# EMG_FSR.net
KiCad netlist of a schematic drawn in EAGLE
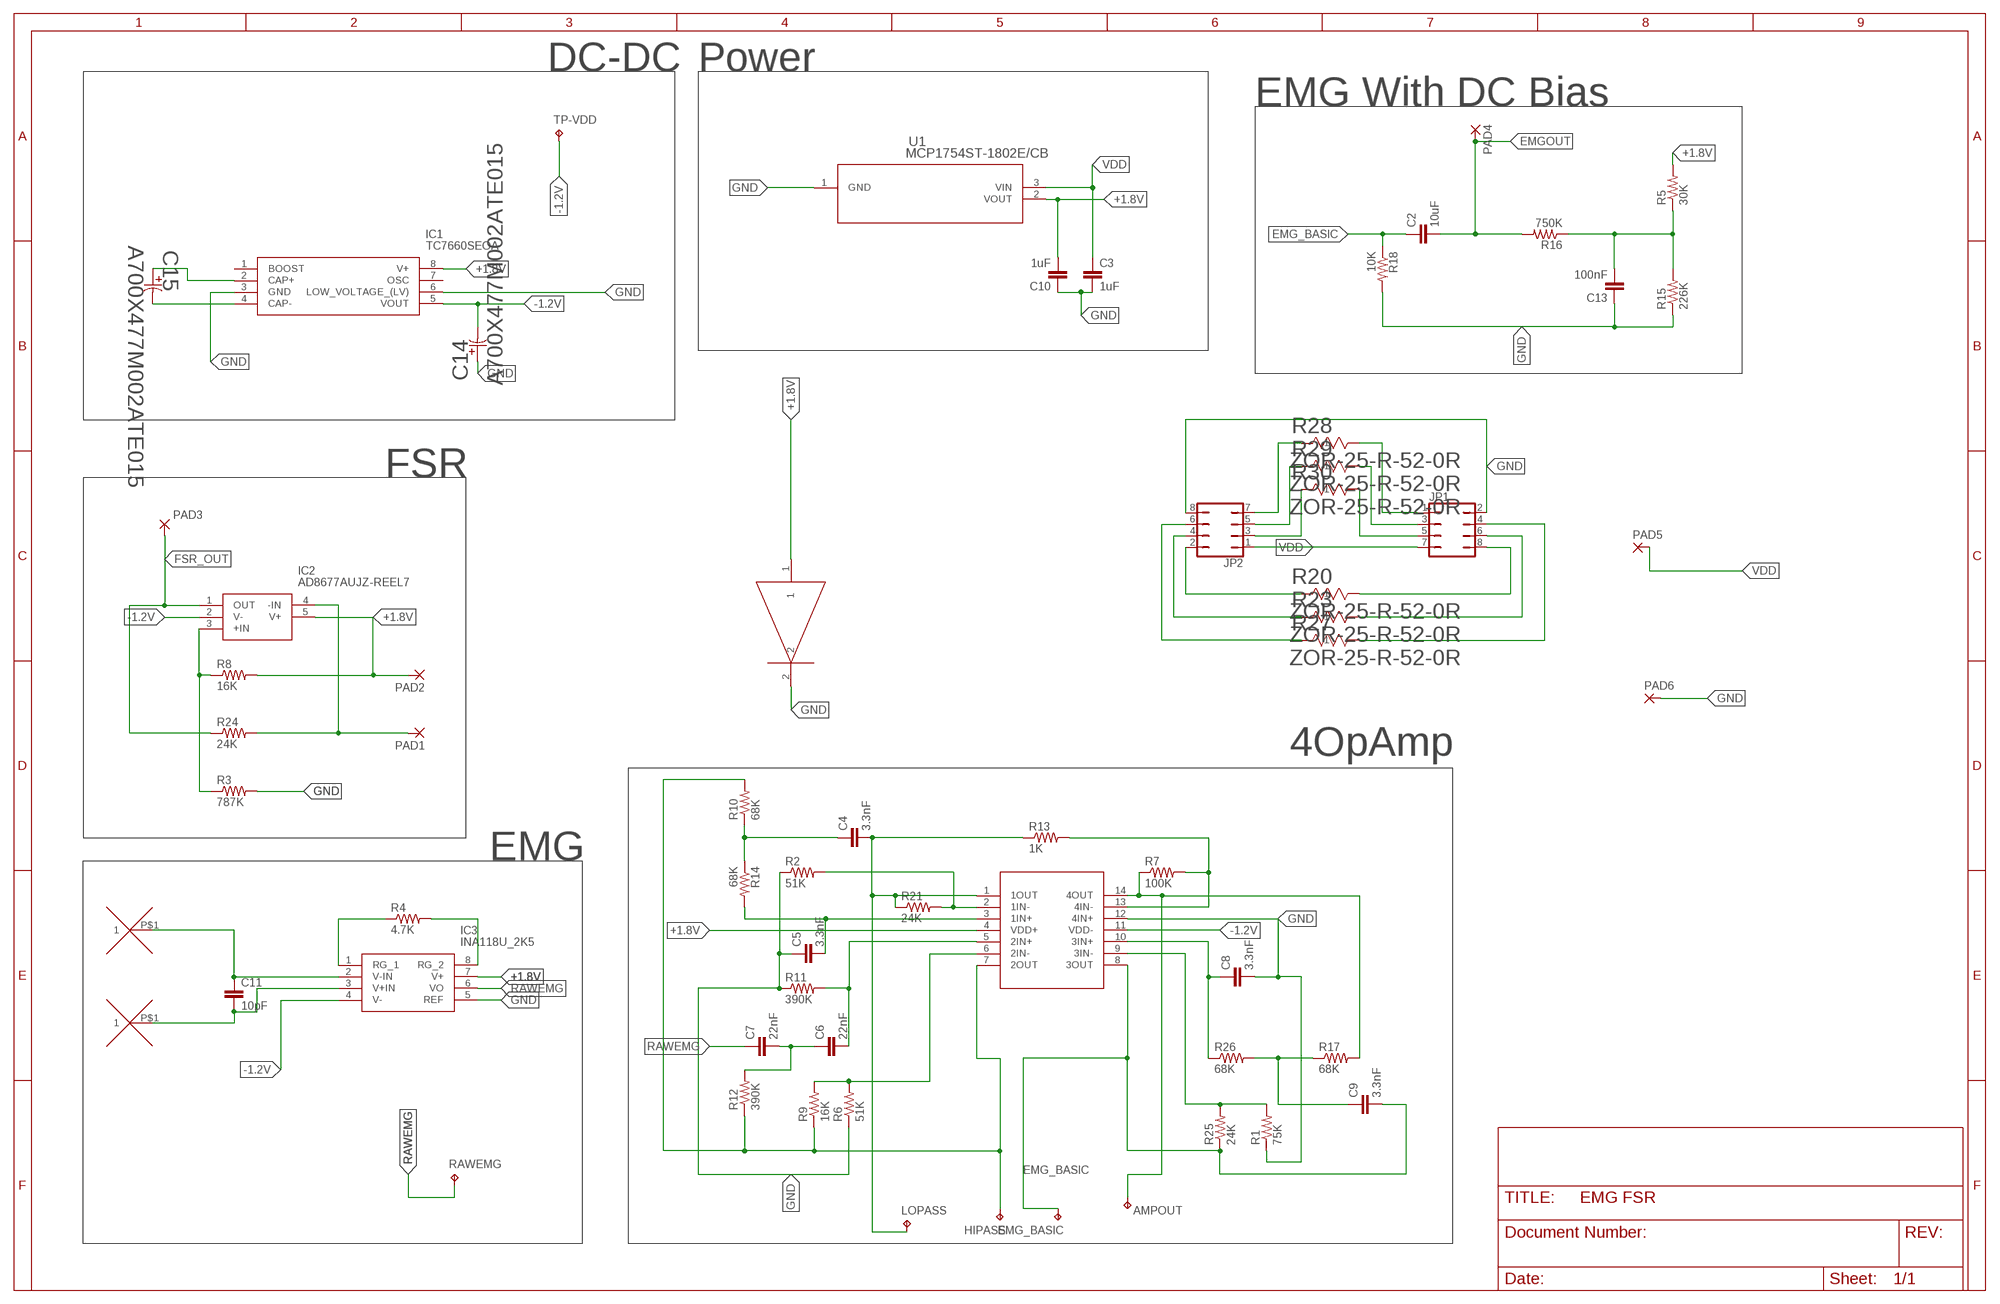
[diagram p0: schematic, sheet 1]

(export (version "E")
  (design (tool "Eeschema 10.0.6"))
  (components
    (comp (ref "AMPOUT")
      (value "TPTP08R")
      (footprint "eagle-import:TP08R")
      (libsource (lib "eagle-import") (part "TPTP08R"))
    )
    (comp (ref "C2")
      (value "10uF")
      (footprint "eagle-import:C0402")
      (libsource (lib "eagle-import") (part "rcl_334_C-EUC0402"))
    )
    (comp (ref "C3")
      (value "1uF")
      (footprint "eagle-import:C0402")
      (libsource (lib "eagle-import") (part "rcl_334_C-EUC0402"))
    )
    (comp (ref "C4")
      (value "3.3nF")
      (footprint "eagle-import:C1206")
      (libsource (lib "eagle-import") (part "C-EUC1206"))
    )
    (comp (ref "C5")
      (value "3.3nF")
      (footprint "eagle-import:C1206")
      (libsource (lib "eagle-import") (part "C-EUC1206"))
    )
    (comp (ref "C6")
      (value "22nF")
      (footprint "eagle-import:C0805")
      (libsource (lib "eagle-import") (part "C-EUC0805"))
    )
    (comp (ref "C7")
      (value "22nF")
      (footprint "eagle-import:C0805")
      (libsource (lib "eagle-import") (part "C-EUC0805"))
    )
    (comp (ref "C8")
      (value "3.3nF")
      (footprint "eagle-import:C1206")
      (libsource (lib "eagle-import") (part "C-EUC1206"))
    )
    (comp (ref "C9")
      (value "3.3nF")
      (footprint "eagle-import:C1206")
      (libsource (lib "eagle-import") (part "C-EUC1206"))
    )
    (comp (ref "C10")
      (value "1uF")
      (footprint "eagle-import:C0402")
      (libsource (lib "eagle-import") (part "rcl_334_C-EUC0402"))
    )
    (comp (ref "C11")
      (value "10pF")
      (footprint "eagle-import:C0402")
      (libsource (lib "eagle-import") (part "rcl_334_C-EUC0402"))
    )
    (comp (ref "C13")
      (value "100nF")
      (footprint "eagle-import:C0402")
      (libsource (lib "eagle-import") (part "rcl_334_C-EUC0402"))
    )
    (comp (ref "C14")
      (value "A700X477M002ATE015")
      (footprint "eagle-import:PCAP7343-43_KEMET_KEM")
      (libsource (lib "eagle-import") (part "A700X477M002ATE015"))
    )
    (comp (ref "C15")
      (value "A700X477M002ATE015")
      (footprint "eagle-import:PCAP7343-43_KEMET_KEM")
      (libsource (lib "eagle-import") (part "A700X477M002ATE015"))
    )
    (comp (ref "EMG_BASIC")
      (value "TPTP08R")
      (footprint "eagle-import:TP08R")
      (libsource (lib "eagle-import") (part "TPTP08R"))
    )
    (comp (ref "HIPASS")
      (value "TPTP08R")
      (footprint "eagle-import:TP08R")
      (libsource (lib "eagle-import") (part "TPTP08R"))
    )
    (comp (ref "IC1")
      (value "TC7660SEOA")
      (footprint "eagle-import:SOIC127P600X175-8N")
      (fields (field (name "MOUSER_PART_NUMBER") "579-TC7660SEOA"))
      (libsource (lib "eagle-import") (part "TC7660SEOA"))
    )
    (comp (ref "IC2")
      (value "AD8677AUJZ-REEL7")
      (footprint "eagle-import:SOT95P280X100-5N")
      (fields (field (name "MOUSER_PART_NUMBER") "584-AD8677AUJZ-R7"))
      (libsource (lib "eagle-import") (part "AD8677AUJZ-REEL7"))
    )
    (comp (ref "IC3")
      (value "INA118U_2K5")
      (footprint "eagle-import:SOIC127P600X175-8N")
      (fields
        (field (name "ARROW_PART_NUMBER") "INA118U/2K5")
        (field (name "MOUSER_PART_NUMBER") "595-INA118U/2K5")
      )
      (libsource (lib "eagle-import") (part "INA118U_2K5"))
    )
    (comp (ref "JP1")
      (value "JP4Q")
      (footprint "eagle-import:JP4Q")
      (libsource (lib "eagle-import") (part "JP4Q"))
    )
    (comp (ref "JP2")
      (value "JP4Q")
      (footprint "eagle-import:JP4Q")
      (libsource (lib "eagle-import") (part "JP4Q"))
    )
    (comp (ref "LOPASS")
      (value "TPTP08R")
      (footprint "eagle-import:TP08R")
      (libsource (lib "eagle-import") (part "TPTP08R"))
    )
    (comp (ref "PAD1")
      (value "SMD2")
      (footprint "eagle-import:SMD1,27-2,54")
      (libsource (lib "eagle-import") (part "SMD2"))
    )
    (comp (ref "PAD2")
      (value "SMD2")
      (footprint "eagle-import:SMD1,27-2,54")
      (libsource (lib "eagle-import") (part "SMD2"))
    )
    (comp (ref "PAD3")
      (value "1,6/0,8")
      (footprint "eagle-import:1,6_0,8")
      (libsource (lib "eagle-import") (part "1,6/0,8"))
    )
    (comp (ref "PAD4")
      (value "1,6/0,8")
      (footprint "eagle-import:1,6_0,8")
      (libsource (lib "eagle-import") (part "1,6/0,8"))
    )
    (comp (ref "PAD5")
      (value "1,6/0,8")
      (footprint "eagle-import:1,6_0,8")
      (libsource (lib "eagle-import") (part "1,6/0,8"))
    )
    (comp (ref "PAD6")
      (value "1,6/0,8")
      (footprint "eagle-import:1,6_0,8")
      (libsource (lib "eagle-import") (part "1,6/0,8"))
    )
    (comp (ref "R1")
      (value "75K")
      (footprint "eagle-import:R0402")
      (libsource (lib "eagle-import") (part "adafruit_420_R-US_R0402"))
    )
    (comp (ref "R2")
      (value "51K")
      (footprint "eagle-import:R0402")
      (libsource (lib "eagle-import") (part "adafruit_420_R-US_R0402"))
    )
    (comp (ref "R3")
      (value "787K")
      (footprint "eagle-import:R0805")
      (libsource (lib "eagle-import") (part "rcl_R-US_R0805"))
    )
    (comp (ref "R4")
      (value "4.7K")
      (footprint "eagle-import:R0402")
      (libsource (lib "eagle-import") (part "adafruit@1_R-US_R0402"))
    )
    (comp (ref "R5")
      (value "30K")
      (footprint "eagle-import:R0402")
      (libsource (lib "eagle-import") (part "adafruit_420_R-US_R0402"))
    )
    (comp (ref "R6")
      (value "51K")
      (footprint "eagle-import:R0402")
      (libsource (lib "eagle-import") (part "adafruit_420_R-US_R0402"))
    )
    (comp (ref "R7")
      (value "100K")
      (footprint "eagle-import:R1005")
      (libsource (lib "eagle-import") (part "adafruit@1_R-US_R1005"))
    )
    (comp (ref "R8")
      (value "16K")
      (footprint "eagle-import:R0402")
      (libsource (lib "eagle-import") (part "adafruit_420_R-US_R0402"))
    )
    (comp (ref "R9")
      (value "16K")
      (footprint "eagle-import:R0402")
      (libsource (lib "eagle-import") (part "adafruit_420_R-US_R0402"))
    )
    (comp (ref "R10")
      (value "68K")
      (footprint "eagle-import:R0402")
      (libsource (lib "eagle-import") (part "adafruit_420_R-US_R0402"))
    )
    (comp (ref "R11")
      (value "390K")
      (footprint "eagle-import:R0603")
      (libsource (lib "eagle-import") (part "R-US_R0603"))
    )
    (comp (ref "R12")
      (value "390K")
      (footprint "eagle-import:R0603")
      (libsource (lib "eagle-import") (part "adafruit@1_R-US_R0603"))
    )
    (comp (ref "R13")
      (value "1K")
      (footprint "eagle-import:R0402")
      (libsource (lib "eagle-import") (part "adafruit_420_R-US_R0402"))
    )
    (comp (ref "R14")
      (value "68K")
      (footprint "eagle-import:R0402")
      (libsource (lib "eagle-import") (part "adafruit_420_R-US_R0402"))
    )
    (comp (ref "R15")
      (value "226K")
      (footprint "eagle-import:R0402")
      (libsource (lib "eagle-import") (part "adafruit_420_R-US_R0402"))
    )
    (comp (ref "R16")
      (value "750K")
      (footprint "eagle-import:R0402")
      (libsource (lib "eagle-import") (part "adafruit_420_R-US_R0402"))
    )
    (comp (ref "R17")
      (value "68K")
      (footprint "eagle-import:R0402")
      (libsource (lib "eagle-import") (part "adafruit_420_R-US_R0402"))
    )
    (comp (ref "R18")
      (value "10K")
      (footprint "eagle-import:R0402")
      (libsource (lib "eagle-import") (part "adafruit_420_R-US_R0402"))
    )
    (comp (ref "R20")
      (value "ZOR-25-R-52-0R")
      (footprint "eagle-import:RES_ZOR25_6P3X2P3_YAG")
      (fields (field (name "COPYRIGHT") "Copyright (C) 2018 Accelerated Designs. All rights reserved"))
      (libsource (lib "eagle-import") (part "ZOR-25-R-52-0R"))
    )
    (comp (ref "R21")
      (value "24K")
      (footprint "eagle-import:R0402")
      (libsource (lib "eagle-import") (part "adafruit_420_R-US_R0402"))
    )
    (comp (ref "R23")
      (value "ZOR-25-R-52-0R")
      (footprint "eagle-import:RES_ZOR25_6P3X2P3_YAG")
      (fields (field (name "COPYRIGHT") "Copyright (C) 2018 Accelerated Designs. All rights reserved"))
      (libsource (lib "eagle-import") (part "ZOR-25-R-52-0R"))
    )
    (comp (ref "R24")
      (value "24K")
      (footprint "eagle-import:R0402")
      (libsource (lib "eagle-import") (part "adafruit_420_R-US_R0402"))
    )
    (comp (ref "R25")
      (value "24K")
      (footprint "eagle-import:R0402")
      (libsource (lib "eagle-import") (part "adafruit_420_R-US_R0402"))
    )
    (comp (ref "R26")
      (value "68K")
      (footprint "eagle-import:R0402")
      (libsource (lib "eagle-import") (part "adafruit_420_R-US_R0402"))
    )
    (comp (ref "R27")
      (value "ZOR-25-R-52-0R")
      (footprint "eagle-import:RES_ZOR25_6P3X2P3_YAG")
      (fields (field (name "COPYRIGHT") "Copyright (C) 2018 Accelerated Designs. All rights reserved"))
      (libsource (lib "eagle-import") (part "ZOR-25-R-52-0R"))
    )
    (comp (ref "R28")
      (value "ZOR-25-R-52-0R")
      (footprint "eagle-import:RES_ZOR25_6P3X2P3_YAG")
      (fields (field (name "COPYRIGHT") "Copyright (C) 2018 Accelerated Designs. All rights reserved"))
      (libsource (lib "eagle-import") (part "ZOR-25-R-52-0R"))
    )
    (comp (ref "R29")
      (value "ZOR-25-R-52-0R")
      (footprint "eagle-import:RES_ZOR25_6P3X2P3_YAG")
      (fields (field (name "COPYRIGHT") "Copyright (C) 2018 Accelerated Designs. All rights reserved"))
      (libsource (lib "eagle-import") (part "ZOR-25-R-52-0R"))
    )
    (comp (ref "R30")
      (value "ZOR-25-R-52-0R")
      (footprint "eagle-import:RES_ZOR25_6P3X2P3_YAG")
      (fields (field (name "COPYRIGHT") "Copyright (C) 2018 Accelerated Designs. All rights reserved"))
      (libsource (lib "eagle-import") (part "ZOR-25-R-52-0R"))
    )
    (comp (ref "RAWEMG")
      (value "TPTP08R")
      (footprint "eagle-import:TP08R")
      (libsource (lib "eagle-import") (part "TPTP08R"))
    )
    (comp (ref "RED")
      (value "RESC0402X40N")
      (footprint "eagle-import:RESC0402X40N")
      (fields (field (name "MANUFACTURER") "KOA"))
      (libsource (lib "eagle-import") (part "RESC0402X40N"))
    )
    (comp (ref "TP-VDD")
      (value "TPTP08R")
      (footprint "eagle-import:TP08R")
      (libsource (lib "eagle-import") (part "TPTP08R"))
    )
    (comp (ref "U$1")
      (value "TLC2274-HT")
      (footprint "eagle-import:SOP65P640X120-14N")
      (libsource (lib "eagle-import") (part "TLC2274-HT"))
    )
    (comp (ref "U$2")
      (value "EMG_VIA")
      (footprint "eagle-import:EMG_VIA")
      (libsource (lib "eagle-import") (part "EMG_VIA"))
    )
    (comp (ref "U$3")
      (value "EMG_VIA")
      (footprint "eagle-import:EMG_VIA")
      (libsource (lib "eagle-import") (part "EMG_VIA"))
    )
    (comp (ref "U1")
      (value "MCP1754ST-1802E/CB")
      (footprint "eagle-import:SOT-23A_MC_MCH")
      (fields (field (name "COPYRIGHT") "Copyright (C) 2018 Accelerated Designs. All rights reserved"))
      (libsource (lib "eagle-import") (part "MCP1754ST-1802E/CB"))
    )
  )
  (nets
    (net (code "1") (name "+1.8V") (class "Default")
      (node (ref "C10") (pin "2") (pinfunction "2_2") (pintype "passive"))
      (node (ref "IC1") (pin "8") (pinfunction "V+_8") (pintype "bidirectional"))
      (node (ref "IC2") (pin "5") (pinfunction "V+_5") (pintype "bidirectional"))
      (node (ref "IC3") (pin "7") (pinfunction "V+_7") (pintype "bidirectional"))
      (node (ref "PAD2") (pin "1") (pinfunction "P_1") (pintype "passive"))
      (node (ref "R5") (pin "2") (pinfunction "2_2") (pintype "passive"))
      (node (ref "R8") (pin "2") (pinfunction "2_2") (pintype "passive"))
      (node (ref "RED") (pin "1") (pinfunction "1_1") (pintype "bidirectional"))
      (node (ref "U$1") (pin "4") (pinfunction "VDD+_4") (pintype "bidirectional"))
      (node (ref "U1") (pin "2") (pinfunction "VOUT_2") (pintype "output"))
    )
    (net (code "2") (name "-1.2V") (class "Default")
      (node (ref "C14") (pin "2") (pinfunction "2_2") (pintype "passive"))
      (node (ref "IC1") (pin "5") (pinfunction "VOUT_5") (pintype "bidirectional"))
      (node (ref "IC2") (pin "2") (pinfunction "V-_2") (pintype "bidirectional"))
      (node (ref "IC3") (pin "4") (pinfunction "V-_4") (pintype "bidirectional"))
      (node (ref "TP-VDD") (pin "TP") (pinfunction "TP_TP") (pintype "input"))
      (node (ref "U$1") (pin "11") (pinfunction "VDD-_11") (pintype "bidirectional"))
    )
    (net (code "3") (name "EMGOUT") (class "Default")
      (node (ref "C2") (pin "2") (pinfunction "2_2") (pintype "passive"))
      (node (ref "PAD4") (pin "1") (pinfunction "P_1") (pintype "passive"))
      (node (ref "R16") (pin "2") (pinfunction "2_2") (pintype "passive"))
    )
    (net (code "4") (name "EMG_BASIC") (class "Default")
      (node (ref "C2") (pin "1") (pinfunction "1_1") (pintype "passive"))
      (node (ref "C9") (pin "2") (pinfunction "2_2") (pintype "passive"))
      (node (ref "EMG_BASIC") (pin "TP") (pinfunction "TP_TP") (pintype "input"))
      (node (ref "R18") (pin "1") (pinfunction "1_1") (pintype "passive"))
      (node (ref "R25") (pin "1") (pinfunction "1_1") (pintype "passive"))
      (node (ref "U$1") (pin "8") (pinfunction "3OUT_8") (pintype "bidirectional"))
    )
    (net (code "5") (name "FSR_OUT") (class "Default")
      (node (ref "IC2") (pin "1") (pinfunction "OUT_1") (pintype "output"))
      (node (ref "PAD3") (pin "1") (pinfunction "P_1") (pintype "passive"))
      (node (ref "R24") (pin "1") (pinfunction "1_1") (pintype "passive"))
    )
    (net (code "6") (name "GND") (class "Default")
      (node (ref "C10") (pin "1") (pinfunction "1_1") (pintype "passive"))
      (node (ref "C13") (pin "1") (pinfunction "1_1") (pintype "passive"))
      (node (ref "C14") (pin "1") (pinfunction "1_1") (pintype "passive"))
      (node (ref "C3") (pin "2") (pinfunction "2_2") (pintype "passive"))
      (node (ref "C5") (pin "1") (pinfunction "1_1") (pintype "passive"))
      (node (ref "C8") (pin "2") (pinfunction "2_2") (pintype "passive"))
      (node (ref "IC1") (pin "3") (pinfunction "GND_3") (pintype "bidirectional"))
      (node (ref "IC1") (pin "6") (pinfunction "LOW_VOLTAGE_(LV)_6") (pintype "bidirectional"))
      (node (ref "IC3") (pin "5") (pinfunction "REF_5") (pintype "bidirectional"))
      (node (ref "JP1") (pin "2") (pinfunction "2_2") (pintype "passive"))
      (node (ref "JP2") (pin "8") (pinfunction "8_8") (pintype "passive"))
      (node (ref "PAD6") (pin "1") (pinfunction "P_1") (pintype "passive"))
      (node (ref "R1") (pin "1") (pinfunction "1_1") (pintype "passive"))
      (node (ref "R11") (pin "1") (pinfunction "1_1") (pintype "passive"))
      (node (ref "R15") (pin "1") (pinfunction "1_1") (pintype "passive"))
      (node (ref "R18") (pin "2") (pinfunction "2_2") (pintype "passive"))
      (node (ref "R2") (pin "1") (pinfunction "1_1") (pintype "passive"))
      (node (ref "R3") (pin "2") (pinfunction "2_2") (pintype "passive"))
      (node (ref "R6") (pin "1") (pinfunction "1_1") (pintype "passive"))
      (node (ref "RED") (pin "2") (pinfunction "2_2") (pintype "bidirectional"))
      (node (ref "U$1") (pin "12") (pinfunction "4IN+_12") (pintype "bidirectional"))
      (node (ref "U1") (pin "1") (pinfunction "GND_1") (pintype "power_in"))
    )
    (net (code "7") (name "Net-(C4-Pad1)") (class "Default")
      (node (ref "C4") (pin "1") (pinfunction "1_1") (pintype "passive"))
      (node (ref "R10") (pin "1") (pinfunction "1_1") (pintype "passive"))
      (node (ref "R14") (pin "1") (pinfunction "1_1") (pintype "passive"))
    )
    (net (code "8") (name "Net-(C6-Pad1)") (class "Default")
      (node (ref "C6") (pin "1") (pinfunction "1_1") (pintype "passive"))
      (node (ref "C7") (pin "2") (pinfunction "2_2") (pintype "passive"))
      (node (ref "R12") (pin "2") (pinfunction "2_2") (pintype "passive"))
    )
    (net (code "9") (name "Net-(C9-Pad1)") (class "Default")
      (node (ref "C9") (pin "1") (pinfunction "1_1") (pintype "passive"))
      (node (ref "R17") (pin "1") (pinfunction "1_1") (pintype "passive"))
      (node (ref "R26") (pin "2") (pinfunction "2_2") (pintype "passive"))
    )
    (net (code "10") (name "Net-(C13-Pad2)") (class "Default")
      (node (ref "C13") (pin "2") (pinfunction "2_2") (pintype "passive"))
      (node (ref "R15") (pin "2") (pinfunction "2_2") (pintype "passive"))
      (node (ref "R16") (pin "1") (pinfunction "1_1") (pintype "passive"))
      (node (ref "R5") (pin "1") (pinfunction "1_1") (pintype "passive"))
    )
    (net (code "11") (name "Net-(IC1-CAP+)") (class "Default")
      (node (ref "C15") (pin "1") (pinfunction "1_1") (pintype "passive"))
      (node (ref "IC1") (pin "2") (pinfunction "CAP+_2") (pintype "bidirectional"))
    )
    (net (code "12") (name "Net-(IC1-CAP-)") (class "Default")
      (node (ref "C15") (pin "2") (pinfunction "2_2") (pintype "passive"))
      (node (ref "IC1") (pin "4") (pinfunction "CAP-_4") (pintype "bidirectional"))
    )
    (net (code "13") (name "Net-(IC2-+IN)") (class "Default")
      (node (ref "IC2") (pin "3") (pinfunction "+IN_3") (pintype "input"))
      (node (ref "R3") (pin "1") (pinfunction "1_1") (pintype "passive"))
      (node (ref "R8") (pin "1") (pinfunction "1_1") (pintype "passive"))
    )
    (net (code "14") (name "Net-(IC2--IN)") (class "Default")
      (node (ref "IC2") (pin "4") (pinfunction "-IN_4") (pintype "input"))
      (node (ref "PAD1") (pin "1") (pinfunction "P_1") (pintype "passive"))
      (node (ref "R24") (pin "2") (pinfunction "2_2") (pintype "passive"))
    )
    (net (code "15") (name "Net-(IC3-RG_1)") (class "Default")
      (node (ref "IC3") (pin "1") (pinfunction "RG_1_1") (pintype "bidirectional"))
      (node (ref "R4") (pin "1") (pinfunction "1_1") (pintype "passive"))
    )
    (net (code "16") (name "Net-(IC3-RG_2)") (class "Default")
      (node (ref "IC3") (pin "8") (pinfunction "RG_2_8") (pintype "bidirectional"))
      (node (ref "R4") (pin "2") (pinfunction "2_2") (pintype "passive"))
    )
    (net (code "17") (name "Net-(IC3-V+IN)") (class "Default")
      (node (ref "C11") (pin "2") (pinfunction "2_2") (pintype "passive"))
      (node (ref "IC3") (pin "3") (pinfunction "V+IN_3") (pintype "bidirectional"))
      (node (ref "U$3") (pin "P$1") (pinfunction "1_P$1") (pintype "bidirectional"))
    )
    (net (code "18") (name "Net-(IC3-V-IN)") (class "Default")
      (node (ref "C11") (pin "1") (pinfunction "1_1") (pintype "passive"))
      (node (ref "IC3") (pin "2") (pinfunction "V-IN_2") (pintype "bidirectional"))
      (node (ref "U$2") (pin "P$1") (pinfunction "1_P$1") (pintype "bidirectional"))
    )
    (net (code "19") (name "Net-(JP1-Pad1)") (class "Default")
      (node (ref "JP1") (pin "1") (pinfunction "1_1") (pintype "passive"))
      (node (ref "R28") (pin "2") (pinfunction "2_2") (pintype "passive"))
    )
    (net (code "20") (name "Net-(JP1-Pad3)") (class "Default")
      (node (ref "JP1") (pin "3") (pinfunction "3_3") (pintype "passive"))
      (node (ref "R29") (pin "2") (pinfunction "2_2") (pintype "passive"))
    )
    (net (code "21") (name "Net-(JP1-Pad4)") (class "Default")
      (node (ref "JP1") (pin "4") (pinfunction "4_4") (pintype "passive"))
      (node (ref "R27") (pin "2") (pinfunction "2_2") (pintype "passive"))
    )
    (net (code "22") (name "Net-(JP1-Pad5)") (class "Default")
      (node (ref "JP1") (pin "5") (pinfunction "5_5") (pintype "passive"))
      (node (ref "R30") (pin "2") (pinfunction "2_2") (pintype "passive"))
    )
    (net (code "23") (name "Net-(JP1-Pad6)") (class "Default")
      (node (ref "JP1") (pin "6") (pinfunction "6_6") (pintype "passive"))
      (node (ref "R23") (pin "2") (pinfunction "2_2") (pintype "passive"))
    )
    (net (code "24") (name "Net-(JP1-Pad8)") (class "Default")
      (node (ref "JP1") (pin "8") (pinfunction "8_8") (pintype "passive"))
      (node (ref "R20") (pin "2") (pinfunction "2_2") (pintype "passive"))
    )
    (net (code "25") (name "Net-(JP2-Pad2)") (class "Default")
      (node (ref "JP2") (pin "2") (pinfunction "2_2") (pintype "passive"))
      (node (ref "R20") (pin "1") (pinfunction "1_1") (pintype "passive"))
    )
    (net (code "26") (name "Net-(JP2-Pad3)") (class "Default")
      (node (ref "JP2") (pin "3") (pinfunction "3_3") (pintype "passive"))
      (node (ref "R30") (pin "1") (pinfunction "1_1") (pintype "passive"))
    )
    (net (code "27") (name "Net-(JP2-Pad4)") (class "Default")
      (node (ref "JP2") (pin "4") (pinfunction "4_4") (pintype "passive"))
      (node (ref "R23") (pin "1") (pinfunction "1_1") (pintype "passive"))
    )
    (net (code "28") (name "Net-(JP2-Pad5)") (class "Default")
      (node (ref "JP2") (pin "5") (pinfunction "5_5") (pintype "passive"))
      (node (ref "R29") (pin "1") (pinfunction "1_1") (pintype "passive"))
    )
    (net (code "29") (name "Net-(JP2-Pad6)") (class "Default")
      (node (ref "JP2") (pin "6") (pinfunction "6_6") (pintype "passive"))
      (node (ref "R27") (pin "1") (pinfunction "1_1") (pintype "passive"))
    )
    (net (code "30") (name "Net-(JP2-Pad7)") (class "Default")
      (node (ref "JP2") (pin "7") (pinfunction "7_7") (pintype "passive"))
      (node (ref "R28") (pin "1") (pinfunction "1_1") (pintype "passive"))
    )
    (net (code "31") (name "Net-(U$1-1IN+)") (class "Default")
      (node (ref "C5") (pin "2") (pinfunction "2_2") (pintype "passive"))
      (node (ref "R14") (pin "2") (pinfunction "2_2") (pintype "passive"))
      (node (ref "U$1") (pin "3") (pinfunction "1IN+_3") (pintype "bidirectional"))
    )
    (net (code "32") (name "Net-(U$1-1IN-)") (class "Default")
      (node (ref "R2") (pin "2") (pinfunction "2_2") (pintype "passive"))
      (node (ref "R21") (pin "2") (pinfunction "2_2") (pintype "passive"))
      (node (ref "U$1") (pin "2") (pinfunction "1IN-_2") (pintype "bidirectional"))
    )
    (net (code "33") (name "Net-(U$1-1OUT)") (class "Default")
      (node (ref "C4") (pin "2") (pinfunction "2_2") (pintype "passive"))
      (node (ref "LOPASS") (pin "TP") (pinfunction "TP_TP") (pintype "input"))
      (node (ref "R13") (pin "1") (pinfunction "1_1") (pintype "passive"))
      (node (ref "R21") (pin "1") (pinfunction "1_1") (pintype "passive"))
      (node (ref "U$1") (pin "1") (pinfunction "1OUT_1") (pintype "bidirectional"))
    )
    (net (code "34") (name "Net-(U$1-2IN+)") (class "Default")
      (node (ref "C6") (pin "2") (pinfunction "2_2") (pintype "passive"))
      (node (ref "R11") (pin "2") (pinfunction "2_2") (pintype "passive"))
      (node (ref "U$1") (pin "5") (pinfunction "2IN+_5") (pintype "bidirectional"))
    )
    (net (code "35") (name "Net-(U$1-2IN-)") (class "Default")
      (node (ref "R6") (pin "2") (pinfunction "2_2") (pintype "passive"))
      (node (ref "R9") (pin "2") (pinfunction "2_2") (pintype "passive"))
      (node (ref "U$1") (pin "6") (pinfunction "2IN-_6") (pintype "bidirectional"))
    )
    (net (code "36") (name "Net-(U$1-2OUT)") (class "Default")
      (node (ref "HIPASS") (pin "TP") (pinfunction "TP_TP") (pintype "input"))
      (node (ref "R10") (pin "2") (pinfunction "2_2") (pintype "passive"))
      (node (ref "R12") (pin "1") (pinfunction "1_1") (pintype "passive"))
      (node (ref "R9") (pin "1") (pinfunction "1_1") (pintype "passive"))
      (node (ref "U$1") (pin "7") (pinfunction "2OUT_7") (pintype "bidirectional"))
    )
    (net (code "37") (name "Net-(U$1-3IN+)") (class "Default")
      (node (ref "C8") (pin "1") (pinfunction "1_1") (pintype "passive"))
      (node (ref "R26") (pin "1") (pinfunction "1_1") (pintype "passive"))
      (node (ref "U$1") (pin "10") (pinfunction "3IN+_10") (pintype "bidirectional"))
    )
    (net (code "38") (name "Net-(U$1-3IN-)") (class "Default")
      (node (ref "R1") (pin "2") (pinfunction "2_2") (pintype "passive"))
      (node (ref "R25") (pin "2") (pinfunction "2_2") (pintype "passive"))
      (node (ref "U$1") (pin "9") (pinfunction "3IN-_9") (pintype "bidirectional"))
    )
    (net (code "39") (name "Net-(U$1-4IN-)") (class "Default")
      (node (ref "R13") (pin "2") (pinfunction "2_2") (pintype "passive"))
      (node (ref "R7") (pin "2") (pinfunction "2_2") (pintype "passive"))
      (node (ref "U$1") (pin "13") (pinfunction "4IN-_13") (pintype "bidirectional"))
    )
    (net (code "40") (name "Net-(U$1-4OUT)") (class "Default")
      (node (ref "AMPOUT") (pin "TP") (pinfunction "TP_TP") (pintype "input"))
      (node (ref "R17") (pin "2") (pinfunction "2_2") (pintype "passive"))
      (node (ref "R7") (pin "1") (pinfunction "1_1") (pintype "passive"))
      (node (ref "U$1") (pin "14") (pinfunction "4OUT_14") (pintype "bidirectional"))
    )
    (net (code "41") (name "RAWEMG") (class "Default")
      (node (ref "C7") (pin "1") (pinfunction "1_1") (pintype "passive"))
      (node (ref "IC3") (pin "6") (pinfunction "VO_6") (pintype "bidirectional"))
      (node (ref "RAWEMG") (pin "TP") (pinfunction "TP_TP") (pintype "input"))
    )
    (net (code "42") (name "VDD") (class "Default")
      (node (ref "C3") (pin "1") (pinfunction "1_1") (pintype "passive"))
      (node (ref "JP1") (pin "7") (pinfunction "7_7") (pintype "passive"))
      (node (ref "JP2") (pin "1") (pinfunction "1_1") (pintype "passive"))
      (node (ref "PAD5") (pin "1") (pinfunction "P_1") (pintype "passive"))
      (node (ref "U1") (pin "3") (pinfunction "VIN_3") (pintype "input"))
    )
    (net (code "43") (name "unconnected-(IC1-BOOST-Pad1)") (class "Default")
      (node (ref "IC1") (pin "1") (pinfunction "BOOST_1") (pintype "bidirectional"))
    )
    (net (code "44") (name "unconnected-(IC1-OSC-Pad7)") (class "Default")
      (node (ref "IC1") (pin "7") (pinfunction "OSC_7") (pintype "bidirectional"))
    )
  )
)
